# project1.net
KiCad netlist of a schematic drawn in EAGLE
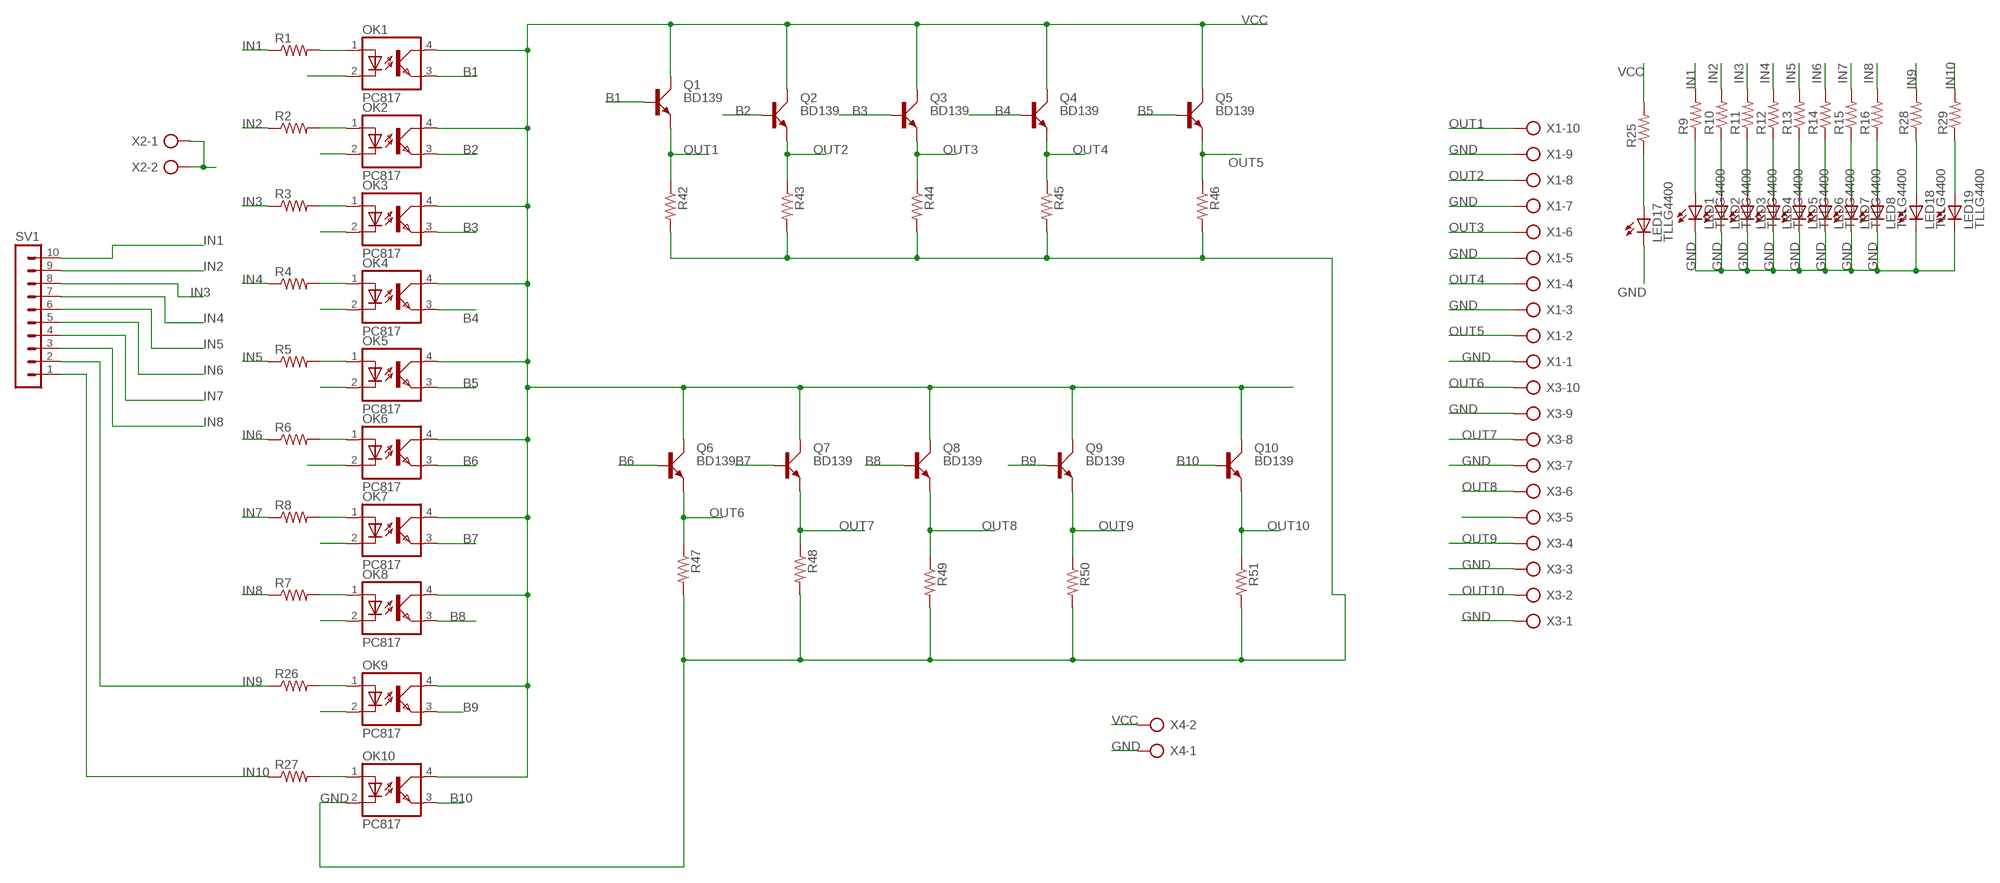
[diagram p0: schematic, sheet 1]

(export (version "E")
  (design (tool "Eeschema 10.0.6"))
  (components
    (comp (ref "LED1")
      (value "TLLG4400")
      (footprint "eagle-import:LED3MM")
      (fields (field (name "MF") "VISHAY SEMICONDUCTOR"))
      (libsource (lib "eagle-import") (part "TLLG4400"))
    )
    (comp (ref "LED2")
      (value "TLLG4400")
      (footprint "eagle-import:LED3MM")
      (fields (field (name "MF") "VISHAY SEMICONDUCTOR"))
      (libsource (lib "eagle-import") (part "TLLG4400"))
    )
    (comp (ref "LED3")
      (value "TLLG4400")
      (footprint "eagle-import:LED3MM")
      (fields (field (name "MF") "VISHAY SEMICONDUCTOR"))
      (libsource (lib "eagle-import") (part "TLLG4400"))
    )
    (comp (ref "LED4")
      (value "TLLG4400")
      (footprint "eagle-import:LED3MM")
      (fields (field (name "MF") "VISHAY SEMICONDUCTOR"))
      (libsource (lib "eagle-import") (part "TLLG4400"))
    )
    (comp (ref "LED5")
      (value "TLLG4400")
      (footprint "eagle-import:LED3MM")
      (fields (field (name "MF") "VISHAY SEMICONDUCTOR"))
      (libsource (lib "eagle-import") (part "TLLG4400"))
    )
    (comp (ref "LED6")
      (value "TLLG4400")
      (footprint "eagle-import:LED3MM")
      (fields (field (name "MF") "VISHAY SEMICONDUCTOR"))
      (libsource (lib "eagle-import") (part "TLLG4400"))
    )
    (comp (ref "LED7")
      (value "TLLG4400")
      (footprint "eagle-import:LED3MM")
      (fields (field (name "MF") "VISHAY SEMICONDUCTOR"))
      (libsource (lib "eagle-import") (part "TLLG4400"))
    )
    (comp (ref "LED8")
      (value "TLLG4400")
      (footprint "eagle-import:LED3MM")
      (fields (field (name "MF") "VISHAY SEMICONDUCTOR"))
      (libsource (lib "eagle-import") (part "TLLG4400"))
    )
    (comp (ref "LED17")
      (value "TLLG4400")
      (footprint "eagle-import:LED3MM")
      (fields (field (name "MF") "VISHAY SEMICONDUCTOR"))
      (libsource (lib "eagle-import") (part "TLLG4400"))
    )
    (comp (ref "LED18")
      (value "TLLG4400")
      (footprint "eagle-import:LED3MM")
      (fields (field (name "MF") "VISHAY SEMICONDUCTOR"))
      (libsource (lib "eagle-import") (part "TLLG4400"))
    )
    (comp (ref "LED19")
      (value "TLLG4400")
      (footprint "eagle-import:LED3MM")
      (fields (field (name "MF") "VISHAY SEMICONDUCTOR"))
      (libsource (lib "eagle-import") (part "TLLG4400"))
    )
    (comp (ref "OK1")
      (value "PC817")
      (footprint "eagle-import:DIL04")
      (fields (field (name "MPN") "PC817X4J000F"))
      (libsource (lib "eagle-import") (part "PC817"))
    )
    (comp (ref "OK2")
      (value "PC817")
      (footprint "eagle-import:DIL04")
      (fields (field (name "MPN") "PC817X4J000F"))
      (libsource (lib "eagle-import") (part "PC817"))
    )
    (comp (ref "OK3")
      (value "PC817")
      (footprint "eagle-import:DIL04")
      (fields (field (name "MPN") "PC817X4J000F"))
      (libsource (lib "eagle-import") (part "PC817"))
    )
    (comp (ref "OK4")
      (value "PC817")
      (footprint "eagle-import:DIL04")
      (fields (field (name "MPN") "PC817X4J000F"))
      (libsource (lib "eagle-import") (part "PC817"))
    )
    (comp (ref "OK5")
      (value "PC817")
      (footprint "eagle-import:DIL04")
      (fields (field (name "MPN") "PC817X4J000F"))
      (libsource (lib "eagle-import") (part "PC817"))
    )
    (comp (ref "OK6")
      (value "PC817")
      (footprint "eagle-import:DIL04")
      (fields (field (name "MPN") "PC817X4J000F"))
      (libsource (lib "eagle-import") (part "PC817"))
    )
    (comp (ref "OK7")
      (value "PC817")
      (footprint "eagle-import:DIL04")
      (fields (field (name "MPN") "PC817X4J000F"))
      (libsource (lib "eagle-import") (part "PC817"))
    )
    (comp (ref "OK8")
      (value "PC817")
      (footprint "eagle-import:DIL04")
      (fields (field (name "MPN") "PC817X4J000F"))
      (libsource (lib "eagle-import") (part "PC817"))
    )
    (comp (ref "OK9")
      (value "PC817")
      (footprint "eagle-import:DIL04")
      (fields (field (name "MPN") "PC817X4J000F"))
      (libsource (lib "eagle-import") (part "PC817"))
    )
    (comp (ref "OK10")
      (value "PC817")
      (footprint "eagle-import:DIL04")
      (fields (field (name "MPN") "PC817X4J000F"))
      (libsource (lib "eagle-import") (part "PC817"))
    )
    (comp (ref "Q1")
      (value "BD139")
      (footprint "eagle-import:TO126AV")
      (libsource (lib "eagle-import") (part "BD139"))
    )
    (comp (ref "Q2")
      (value "BD139")
      (footprint "eagle-import:TO126AV")
      (libsource (lib "eagle-import") (part "BD139"))
    )
    (comp (ref "Q3")
      (value "BD139")
      (footprint "eagle-import:TO126AV")
      (libsource (lib "eagle-import") (part "BD139"))
    )
    (comp (ref "Q4")
      (value "BD139")
      (footprint "eagle-import:TO126AV")
      (libsource (lib "eagle-import") (part "BD139"))
    )
    (comp (ref "Q5")
      (value "BD139")
      (footprint "eagle-import:TO126AV")
      (libsource (lib "eagle-import") (part "BD139"))
    )
    (comp (ref "Q6")
      (value "BD139")
      (footprint "eagle-import:TO126AV")
      (libsource (lib "eagle-import") (part "BD139"))
    )
    (comp (ref "Q7")
      (value "BD139")
      (footprint "eagle-import:TO126AV")
      (libsource (lib "eagle-import") (part "BD139"))
    )
    (comp (ref "Q8")
      (value "BD139")
      (footprint "eagle-import:TO126AV")
      (libsource (lib "eagle-import") (part "BD139"))
    )
    (comp (ref "Q9")
      (value "BD139")
      (footprint "eagle-import:TO126AV")
      (libsource (lib "eagle-import") (part "BD139"))
    )
    (comp (ref "Q10")
      (value "BD139")
      (footprint "eagle-import:TO126AV")
      (libsource (lib "eagle-import") (part "BD139"))
    )
    (comp (ref "R1")
      (value "R-US_0207/10")
      (footprint "eagle-import:0207_10")
      (libsource (lib "eagle-import") (part "resistor_R-US_0207/10"))
    )
    (comp (ref "R2")
      (value "R-US_0207/10")
      (footprint "eagle-import:0207_10")
      (libsource (lib "eagle-import") (part "R-US_0207/10"))
    )
    (comp (ref "R3")
      (value "R-US_0207/10")
      (footprint "eagle-import:0207_10")
      (libsource (lib "eagle-import") (part "R-US_0207/10"))
    )
    (comp (ref "R4")
      (value "R-US_0207/10")
      (footprint "eagle-import:0207_10")
      (libsource (lib "eagle-import") (part "R-US_0207/10"))
    )
    (comp (ref "R5")
      (value "R-US_0207/10")
      (footprint "eagle-import:0207_10")
      (libsource (lib "eagle-import") (part "R-US_0207/10"))
    )
    (comp (ref "R6")
      (value "R-US_0207/10")
      (footprint "eagle-import:0207_10")
      (libsource (lib "eagle-import") (part "R-US_0207/10"))
    )
    (comp (ref "R7")
      (value "R-US_0207/10")
      (footprint "eagle-import:0207_10")
      (libsource (lib "eagle-import") (part "R-US_0207/10"))
    )
    (comp (ref "R8")
      (value "R-US_0207/10")
      (footprint "eagle-import:0207_10")
      (libsource (lib "eagle-import") (part "R-US_0207/10"))
    )
    (comp (ref "R9")
      (value "R-US_0207/10")
      (footprint "eagle-import:0207_10")
      (libsource (lib "eagle-import") (part "R-US_0207/10"))
    )
    (comp (ref "R10")
      (value "R-US_0207/10")
      (footprint "eagle-import:0207_10")
      (libsource (lib "eagle-import") (part "R-US_0207/10"))
    )
    (comp (ref "R11")
      (value "R-US_0207/10")
      (footprint "eagle-import:0207_10")
      (libsource (lib "eagle-import") (part "R-US_0207/10"))
    )
    (comp (ref "R12")
      (value "R-US_0207/10")
      (footprint "eagle-import:0207_10")
      (libsource (lib "eagle-import") (part "R-US_0207/10"))
    )
    (comp (ref "R13")
      (value "R-US_0207/10")
      (footprint "eagle-import:0207_10")
      (libsource (lib "eagle-import") (part "R-US_0207/10"))
    )
    (comp (ref "R14")
      (value "R-US_0207/10")
      (footprint "eagle-import:0207_10")
      (libsource (lib "eagle-import") (part "R-US_0207/10"))
    )
    (comp (ref "R15")
      (value "R-US_0207/10")
      (footprint "eagle-import:0207_10")
      (libsource (lib "eagle-import") (part "R-US_0207/10"))
    )
    (comp (ref "R16")
      (value "R-US_0207/10")
      (footprint "eagle-import:0207_10")
      (libsource (lib "eagle-import") (part "R-US_0207/10"))
    )
    (comp (ref "R25")
      (value "R-US_0207/10")
      (footprint "eagle-import:0207_10")
      (libsource (lib "eagle-import") (part "R-US_0207/10"))
    )
    (comp (ref "R26")
      (value "R-US_0207/10")
      (footprint "eagle-import:0207_10")
      (libsource (lib "eagle-import") (part "R-US_0207/10"))
    )
    (comp (ref "R27")
      (value "R-US_0207/10")
      (footprint "eagle-import:0207_10")
      (libsource (lib "eagle-import") (part "R-US_0207/10"))
    )
    (comp (ref "R28")
      (value "R-US_0207/10")
      (footprint "eagle-import:0207_10")
      (libsource (lib "eagle-import") (part "R-US_0207/10"))
    )
    (comp (ref "R29")
      (value "R-US_0207/10")
      (footprint "eagle-import:0207_10")
      (libsource (lib "eagle-import") (part "R-US_0207/10"))
    )
    (comp (ref "R42")
      (value "R-US_0207/10")
      (footprint "eagle-import:0207_10")
      (libsource (lib "eagle-import") (part "resistor_R-US_0207/10"))
    )
    (comp (ref "R43")
      (value "R-US_0207/10")
      (footprint "eagle-import:0207_10")
      (libsource (lib "eagle-import") (part "resistor_R-US_0207/10"))
    )
    (comp (ref "R44")
      (value "R-US_0207/10")
      (footprint "eagle-import:0207_10")
      (libsource (lib "eagle-import") (part "resistor_R-US_0207/10"))
    )
    (comp (ref "R45")
      (value "R-US_0207/10")
      (footprint "eagle-import:0207_10")
      (libsource (lib "eagle-import") (part "resistor_R-US_0207/10"))
    )
    (comp (ref "R46")
      (value "R-US_0207/10")
      (footprint "eagle-import:0207_10")
      (libsource (lib "eagle-import") (part "resistor_R-US_0207/10"))
    )
    (comp (ref "R47")
      (value "R-US_0207/10")
      (footprint "eagle-import:0207_10")
      (libsource (lib "eagle-import") (part "resistor_R-US_0207/10"))
    )
    (comp (ref "R48")
      (value "R-US_0207/10")
      (footprint "eagle-import:0207_10")
      (libsource (lib "eagle-import") (part "resistor_R-US_0207/10"))
    )
    (comp (ref "R49")
      (value "R-US_0207/10")
      (footprint "eagle-import:0207_10")
      (libsource (lib "eagle-import") (part "resistor_R-US_0207/10"))
    )
    (comp (ref "R50")
      (value "R-US_0207/10")
      (footprint "eagle-import:0207_10")
      (libsource (lib "eagle-import") (part "resistor_R-US_0207/10"))
    )
    (comp (ref "R51")
      (value "R-US_0207/10")
      (footprint "eagle-import:0207_10")
      (libsource (lib "eagle-import") (part "resistor_R-US_0207/10"))
    )
    (comp (ref "SV1")
      (value "MA10-1")
      (footprint "eagle-import:MA10-1")
      (libsource (lib "eagle-import") (part "MA10-1"))
    )
    (comp (ref "X1")
      (value "AK300/10")
      (footprint "eagle-import:AK300_10")
      (libsource (lib "eagle-import") (part "AK300/10"))
    )
    (comp (ref "X2")
      (value "AK300/2")
      (footprint "eagle-import:AK300_2")
      (libsource (lib "eagle-import") (part "AK300/2"))
    )
    (comp (ref "X3")
      (value "AK300/10")
      (footprint "eagle-import:AK300_10")
      (libsource (lib "eagle-import") (part "AK300/10"))
    )
    (comp (ref "X4")
      (value "AK300/2")
      (footprint "eagle-import:AK300_2")
      (libsource (lib "eagle-import") (part "AK300/2"))
    )
  )
  (nets
    (net (code "1") (name "/B1") (class "Default")
      (node (ref "OK1") (pin "3") (pinfunction "EMIT_3") (pintype "passive"))
      (node (ref "Q1") (pin "B") (pinfunction "B_B") (pintype "passive"))
    )
    (net (code "2") (name "/B2") (class "Default")
      (node (ref "OK2") (pin "3") (pinfunction "EMIT_3") (pintype "passive"))
      (node (ref "Q2") (pin "B") (pinfunction "B_B") (pintype "passive"))
    )
    (net (code "3") (name "/B3") (class "Default")
      (node (ref "OK3") (pin "3") (pinfunction "EMIT_3") (pintype "passive"))
      (node (ref "Q3") (pin "B") (pinfunction "B_B") (pintype "passive"))
    )
    (net (code "4") (name "/B4") (class "Default")
      (node (ref "OK4") (pin "3") (pinfunction "EMIT_3") (pintype "passive"))
      (node (ref "Q4") (pin "B") (pinfunction "B_B") (pintype "passive"))
    )
    (net (code "5") (name "/B5") (class "Default")
      (node (ref "OK5") (pin "3") (pinfunction "EMIT_3") (pintype "passive"))
      (node (ref "Q5") (pin "B") (pinfunction "B_B") (pintype "passive"))
    )
    (net (code "6") (name "/B6") (class "Default")
      (node (ref "OK6") (pin "3") (pinfunction "EMIT_3") (pintype "passive"))
      (node (ref "Q6") (pin "B") (pinfunction "B_B") (pintype "passive"))
    )
    (net (code "7") (name "/B7") (class "Default")
      (node (ref "OK7") (pin "3") (pinfunction "EMIT_3") (pintype "passive"))
      (node (ref "Q7") (pin "B") (pinfunction "B_B") (pintype "passive"))
    )
    (net (code "8") (name "/B8") (class "Default")
      (node (ref "OK8") (pin "3") (pinfunction "EMIT_3") (pintype "passive"))
      (node (ref "Q8") (pin "B") (pinfunction "B_B") (pintype "passive"))
    )
    (net (code "9") (name "/B9") (class "Default")
      (node (ref "OK9") (pin "3") (pinfunction "EMIT_3") (pintype "passive"))
      (node (ref "Q9") (pin "B") (pinfunction "B_B") (pintype "passive"))
    )
    (net (code "10") (name "/B10") (class "Default")
      (node (ref "OK10") (pin "3") (pinfunction "EMIT_3") (pintype "passive"))
      (node (ref "Q10") (pin "B") (pinfunction "B_B") (pintype "passive"))
    )
    (net (code "11") (name "/GND") (class "Default")
      (node (ref "LED1") (pin "K") (pinfunction "C_K") (pintype "passive"))
      (node (ref "LED17") (pin "K") (pinfunction "C_K") (pintype "passive"))
      (node (ref "LED18") (pin "K") (pinfunction "C_K") (pintype "passive"))
      (node (ref "LED19") (pin "K") (pinfunction "C_K") (pintype "passive"))
      (node (ref "LED2") (pin "K") (pinfunction "C_K") (pintype "passive"))
      (node (ref "LED3") (pin "K") (pinfunction "C_K") (pintype "passive"))
      (node (ref "LED4") (pin "K") (pinfunction "C_K") (pintype "passive"))
      (node (ref "LED5") (pin "K") (pinfunction "C_K") (pintype "passive"))
      (node (ref "LED6") (pin "K") (pinfunction "C_K") (pintype "passive"))
      (node (ref "LED7") (pin "K") (pinfunction "C_K") (pintype "passive"))
      (node (ref "LED8") (pin "K") (pinfunction "C_K") (pintype "passive"))
      (node (ref "OK1") (pin "2") (pinfunction "C_2") (pintype "passive"))
      (node (ref "OK10") (pin "2") (pinfunction "C_2") (pintype "passive"))
      (node (ref "OK2") (pin "2") (pinfunction "C_2") (pintype "passive"))
      (node (ref "OK3") (pin "2") (pinfunction "C_2") (pintype "passive"))
      (node (ref "OK4") (pin "2") (pinfunction "C_2") (pintype "passive"))
      (node (ref "OK5") (pin "2") (pinfunction "C_2") (pintype "passive"))
      (node (ref "OK6") (pin "2") (pinfunction "C_2") (pintype "passive"))
      (node (ref "OK7") (pin "2") (pinfunction "C_2") (pintype "passive"))
      (node (ref "OK8") (pin "2") (pinfunction "C_2") (pintype "passive"))
      (node (ref "OK9") (pin "2") (pinfunction "C_2") (pintype "passive"))
      (node (ref "R42") (pin "2") (pinfunction "2_2") (pintype "passive"))
      (node (ref "R43") (pin "2") (pinfunction "2_2") (pintype "passive"))
      (node (ref "R44") (pin "2") (pinfunction "2_2") (pintype "passive"))
      (node (ref "R45") (pin "2") (pinfunction "2_2") (pintype "passive"))
      (node (ref "R46") (pin "2") (pinfunction "2_2") (pintype "passive"))
      (node (ref "R47") (pin "2") (pinfunction "2_2") (pintype "passive"))
      (node (ref "R48") (pin "2") (pinfunction "2_2") (pintype "passive"))
      (node (ref "R49") (pin "2") (pinfunction "2_2") (pintype "passive"))
      (node (ref "R50") (pin "2") (pinfunction "2_2") (pintype "passive"))
      (node (ref "R51") (pin "2") (pinfunction "2_2") (pintype "passive"))
      (node (ref "X1") (pin "1") (pinfunction "KL_1") (pintype "passive"))
      (node (ref "X1") (pin "3") (pinfunction "KL_3") (pintype "passive"))
      (node (ref "X1") (pin "5") (pinfunction "KL_5") (pintype "passive"))
      (node (ref "X1") (pin "7") (pinfunction "KL_7") (pintype "passive"))
      (node (ref "X1") (pin "9") (pinfunction "KL_9") (pintype "passive"))
      (node (ref "X2") (pin "1") (pinfunction "KL_1") (pintype "passive"))
      (node (ref "X2") (pin "2") (pinfunction "KL_2") (pintype "passive"))
      (node (ref "X3") (pin "1") (pinfunction "KL_1") (pintype "passive"))
      (node (ref "X3") (pin "3") (pinfunction "KL_3") (pintype "passive"))
      (node (ref "X3") (pin "5") (pinfunction "KL_5") (pintype "passive"))
      (node (ref "X3") (pin "7") (pinfunction "KL_7") (pintype "passive"))
      (node (ref "X3") (pin "9") (pinfunction "KL_9") (pintype "passive"))
      (node (ref "X4") (pin "1") (pinfunction "KL_1") (pintype "passive"))
    )
    (net (code "12") (name "/IN1") (class "Default")
      (node (ref "R1") (pin "1") (pinfunction "1_1") (pintype "passive"))
      (node (ref "R9") (pin "2") (pinfunction "2_2") (pintype "passive"))
      (node (ref "SV1") (pin "10") (pinfunction "10_10") (pintype "passive"))
    )
    (net (code "13") (name "/IN2") (class "Default")
      (node (ref "R10") (pin "2") (pinfunction "2_2") (pintype "passive"))
      (node (ref "R2") (pin "1") (pinfunction "1_1") (pintype "passive"))
      (node (ref "SV1") (pin "9") (pinfunction "9_9") (pintype "passive"))
    )
    (net (code "14") (name "/IN3") (class "Default")
      (node (ref "R11") (pin "2") (pinfunction "2_2") (pintype "passive"))
      (node (ref "R3") (pin "1") (pinfunction "1_1") (pintype "passive"))
      (node (ref "SV1") (pin "8") (pinfunction "8_8") (pintype "passive"))
    )
    (net (code "15") (name "/IN4") (class "Default")
      (node (ref "R12") (pin "2") (pinfunction "2_2") (pintype "passive"))
      (node (ref "R4") (pin "1") (pinfunction "1_1") (pintype "passive"))
      (node (ref "SV1") (pin "7") (pinfunction "7_7") (pintype "passive"))
    )
    (net (code "16") (name "/IN5") (class "Default")
      (node (ref "R13") (pin "2") (pinfunction "2_2") (pintype "passive"))
      (node (ref "R5") (pin "1") (pinfunction "1_1") (pintype "passive"))
      (node (ref "SV1") (pin "6") (pinfunction "6_6") (pintype "passive"))
    )
    (net (code "17") (name "/IN6") (class "Default")
      (node (ref "R14") (pin "2") (pinfunction "2_2") (pintype "passive"))
      (node (ref "R6") (pin "1") (pinfunction "1_1") (pintype "passive"))
      (node (ref "SV1") (pin "5") (pinfunction "5_5") (pintype "passive"))
    )
    (net (code "18") (name "/IN7") (class "Default")
      (node (ref "R15") (pin "2") (pinfunction "2_2") (pintype "passive"))
      (node (ref "R8") (pin "1") (pinfunction "1_1") (pintype "passive"))
      (node (ref "SV1") (pin "4") (pinfunction "4_4") (pintype "passive"))
    )
    (net (code "19") (name "/IN8") (class "Default")
      (node (ref "R16") (pin "2") (pinfunction "2_2") (pintype "passive"))
      (node (ref "R7") (pin "1") (pinfunction "1_1") (pintype "passive"))
      (node (ref "SV1") (pin "3") (pinfunction "3_3") (pintype "passive"))
    )
    (net (code "20") (name "/IN9") (class "Default")
      (node (ref "R26") (pin "1") (pinfunction "1_1") (pintype "passive"))
      (node (ref "R28") (pin "2") (pinfunction "2_2") (pintype "passive"))
      (node (ref "SV1") (pin "2") (pinfunction "2_2") (pintype "passive"))
    )
    (net (code "21") (name "/IN10") (class "Default")
      (node (ref "R27") (pin "1") (pinfunction "1_1") (pintype "passive"))
      (node (ref "R29") (pin "2") (pinfunction "2_2") (pintype "passive"))
      (node (ref "SV1") (pin "1") (pinfunction "1_1") (pintype "passive"))
    )
    (net (code "22") (name "/OUT1") (class "Default")
      (node (ref "Q1") (pin "E") (pinfunction "E_E") (pintype "passive"))
      (node (ref "R42") (pin "1") (pinfunction "1_1") (pintype "passive"))
      (node (ref "X1") (pin "10") (pinfunction "KL_10") (pintype "passive"))
    )
    (net (code "23") (name "/OUT2") (class "Default")
      (node (ref "Q2") (pin "E") (pinfunction "E_E") (pintype "passive"))
      (node (ref "R43") (pin "1") (pinfunction "1_1") (pintype "passive"))
      (node (ref "X1") (pin "8") (pinfunction "KL_8") (pintype "passive"))
    )
    (net (code "24") (name "/OUT3") (class "Default")
      (node (ref "Q3") (pin "E") (pinfunction "E_E") (pintype "passive"))
      (node (ref "R44") (pin "1") (pinfunction "1_1") (pintype "passive"))
      (node (ref "X1") (pin "6") (pinfunction "KL_6") (pintype "passive"))
    )
    (net (code "25") (name "/OUT4") (class "Default")
      (node (ref "Q4") (pin "E") (pinfunction "E_E") (pintype "passive"))
      (node (ref "R45") (pin "1") (pinfunction "1_1") (pintype "passive"))
      (node (ref "X1") (pin "4") (pinfunction "KL_4") (pintype "passive"))
    )
    (net (code "26") (name "/OUT5") (class "Default")
      (node (ref "Q5") (pin "E") (pinfunction "E_E") (pintype "passive"))
      (node (ref "R46") (pin "1") (pinfunction "1_1") (pintype "passive"))
      (node (ref "X1") (pin "2") (pinfunction "KL_2") (pintype "passive"))
    )
    (net (code "27") (name "/OUT6") (class "Default")
      (node (ref "Q6") (pin "E") (pinfunction "E_E") (pintype "passive"))
      (node (ref "R47") (pin "1") (pinfunction "1_1") (pintype "passive"))
      (node (ref "X3") (pin "10") (pinfunction "KL_10") (pintype "passive"))
    )
    (net (code "28") (name "/OUT7") (class "Default")
      (node (ref "Q7") (pin "E") (pinfunction "E_E") (pintype "passive"))
      (node (ref "R48") (pin "1") (pinfunction "1_1") (pintype "passive"))
      (node (ref "X3") (pin "8") (pinfunction "KL_8") (pintype "passive"))
    )
    (net (code "29") (name "/OUT8") (class "Default")
      (node (ref "Q8") (pin "E") (pinfunction "E_E") (pintype "passive"))
      (node (ref "R49") (pin "1") (pinfunction "1_1") (pintype "passive"))
      (node (ref "X3") (pin "6") (pinfunction "KL_6") (pintype "passive"))
    )
    (net (code "30") (name "/OUT9") (class "Default")
      (node (ref "Q9") (pin "E") (pinfunction "E_E") (pintype "passive"))
      (node (ref "R50") (pin "1") (pinfunction "1_1") (pintype "passive"))
      (node (ref "X3") (pin "4") (pinfunction "KL_4") (pintype "passive"))
    )
    (net (code "31") (name "/OUT10") (class "Default")
      (node (ref "Q10") (pin "E") (pinfunction "E_E") (pintype "passive"))
      (node (ref "R51") (pin "1") (pinfunction "1_1") (pintype "passive"))
      (node (ref "X3") (pin "2") (pinfunction "KL_2") (pintype "passive"))
    )
    (net (code "32") (name "/VCC") (class "Default")
      (node (ref "OK1") (pin "4") (pinfunction "COL_4") (pintype "passive"))
      (node (ref "OK10") (pin "4") (pinfunction "COL_4") (pintype "passive"))
      (node (ref "OK2") (pin "4") (pinfunction "COL_4") (pintype "passive"))
      (node (ref "OK3") (pin "4") (pinfunction "COL_4") (pintype "passive"))
      (node (ref "OK4") (pin "4") (pinfunction "COL_4") (pintype "passive"))
      (node (ref "OK5") (pin "4") (pinfunction "COL_4") (pintype "passive"))
      (node (ref "OK6") (pin "4") (pinfunction "COL_4") (pintype "passive"))
      (node (ref "OK7") (pin "4") (pinfunction "COL_4") (pintype "passive"))
      (node (ref "OK8") (pin "4") (pinfunction "COL_4") (pintype "passive"))
      (node (ref "OK9") (pin "4") (pinfunction "COL_4") (pintype "passive"))
      (node (ref "Q1") (pin "C") (pinfunction "C_C") (pintype "passive"))
      (node (ref "Q10") (pin "C") (pinfunction "C_C") (pintype "passive"))
      (node (ref "Q2") (pin "C") (pinfunction "C_C") (pintype "passive"))
      (node (ref "Q3") (pin "C") (pinfunction "C_C") (pintype "passive"))
      (node (ref "Q4") (pin "C") (pinfunction "C_C") (pintype "passive"))
      (node (ref "Q5") (pin "C") (pinfunction "C_C") (pintype "passive"))
      (node (ref "Q6") (pin "C") (pinfunction "C_C") (pintype "passive"))
      (node (ref "Q7") (pin "C") (pinfunction "C_C") (pintype "passive"))
      (node (ref "Q8") (pin "C") (pinfunction "C_C") (pintype "passive"))
      (node (ref "Q9") (pin "C") (pinfunction "C_C") (pintype "passive"))
      (node (ref "R25") (pin "2") (pinfunction "2_2") (pintype "passive"))
      (node (ref "X4") (pin "2") (pinfunction "KL_2") (pintype "passive"))
    )
    (net (code "33") (name "Net-(LED1-PadA)") (class "Default")
      (node (ref "LED1") (pin "A") (pinfunction "A_A") (pintype "passive"))
      (node (ref "R9") (pin "1") (pinfunction "1_1") (pintype "passive"))
    )
    (net (code "34") (name "Net-(LED2-PadA)") (class "Default")
      (node (ref "LED2") (pin "A") (pinfunction "A_A") (pintype "passive"))
      (node (ref "R10") (pin "1") (pinfunction "1_1") (pintype "passive"))
    )
    (net (code "35") (name "Net-(LED3-PadA)") (class "Default")
      (node (ref "LED3") (pin "A") (pinfunction "A_A") (pintype "passive"))
      (node (ref "R11") (pin "1") (pinfunction "1_1") (pintype "passive"))
    )
    (net (code "36") (name "Net-(LED4-PadA)") (class "Default")
      (node (ref "LED4") (pin "A") (pinfunction "A_A") (pintype "passive"))
      (node (ref "R12") (pin "1") (pinfunction "1_1") (pintype "passive"))
    )
    (net (code "37") (name "Net-(LED5-PadA)") (class "Default")
      (node (ref "LED5") (pin "A") (pinfunction "A_A") (pintype "passive"))
      (node (ref "R13") (pin "1") (pinfunction "1_1") (pintype "passive"))
    )
    (net (code "38") (name "Net-(LED6-PadA)") (class "Default")
      (node (ref "LED6") (pin "A") (pinfunction "A_A") (pintype "passive"))
      (node (ref "R14") (pin "1") (pinfunction "1_1") (pintype "passive"))
    )
    (net (code "39") (name "Net-(LED7-PadA)") (class "Default")
      (node (ref "LED7") (pin "A") (pinfunction "A_A") (pintype "passive"))
      (node (ref "R15") (pin "1") (pinfunction "1_1") (pintype "passive"))
    )
    (net (code "40") (name "Net-(LED8-PadA)") (class "Default")
      (node (ref "LED8") (pin "A") (pinfunction "A_A") (pintype "passive"))
      (node (ref "R16") (pin "1") (pinfunction "1_1") (pintype "passive"))
    )
    (net (code "41") (name "Net-(LED17-PadA)") (class "Default")
      (node (ref "LED17") (pin "A") (pinfunction "A_A") (pintype "passive"))
      (node (ref "R25") (pin "1") (pinfunction "1_1") (pintype "passive"))
    )
    (net (code "42") (name "Net-(LED18-PadA)") (class "Default")
      (node (ref "LED18") (pin "A") (pinfunction "A_A") (pintype "passive"))
      (node (ref "R28") (pin "1") (pinfunction "1_1") (pintype "passive"))
    )
    (net (code "43") (name "Net-(LED19-PadA)") (class "Default")
      (node (ref "LED19") (pin "A") (pinfunction "A_A") (pintype "passive"))
      (node (ref "R29") (pin "1") (pinfunction "1_1") (pintype "passive"))
    )
    (net (code "44") (name "Net-(OK1-A)") (class "Default")
      (node (ref "OK1") (pin "1") (pinfunction "A_1") (pintype "passive"))
      (node (ref "R1") (pin "2") (pinfunction "2_2") (pintype "passive"))
    )
    (net (code "45") (name "Net-(OK2-A)") (class "Default")
      (node (ref "OK2") (pin "1") (pinfunction "A_1") (pintype "passive"))
      (node (ref "R2") (pin "2") (pinfunction "2_2") (pintype "passive"))
    )
    (net (code "46") (name "Net-(OK3-A)") (class "Default")
      (node (ref "OK3") (pin "1") (pinfunction "A_1") (pintype "passive"))
      (node (ref "R3") (pin "2") (pinfunction "2_2") (pintype "passive"))
    )
    (net (code "47") (name "Net-(OK4-A)") (class "Default")
      (node (ref "OK4") (pin "1") (pinfunction "A_1") (pintype "passive"))
      (node (ref "R4") (pin "2") (pinfunction "2_2") (pintype "passive"))
    )
    (net (code "48") (name "Net-(OK5-A)") (class "Default")
      (node (ref "OK5") (pin "1") (pinfunction "A_1") (pintype "passive"))
      (node (ref "R5") (pin "2") (pinfunction "2_2") (pintype "passive"))
    )
    (net (code "49") (name "Net-(OK6-A)") (class "Default")
      (node (ref "OK6") (pin "1") (pinfunction "A_1") (pintype "passive"))
      (node (ref "R6") (pin "2") (pinfunction "2_2") (pintype "passive"))
    )
    (net (code "50") (name "Net-(OK7-A)") (class "Default")
      (node (ref "OK7") (pin "1") (pinfunction "A_1") (pintype "passive"))
      (node (ref "R8") (pin "2") (pinfunction "2_2") (pintype "passive"))
    )
    (net (code "51") (name "Net-(OK8-A)") (class "Default")
      (node (ref "OK8") (pin "1") (pinfunction "A_1") (pintype "passive"))
      (node (ref "R7") (pin "2") (pinfunction "2_2") (pintype "passive"))
    )
    (net (code "52") (name "Net-(OK9-A)") (class "Default")
      (node (ref "OK9") (pin "1") (pinfunction "A_1") (pintype "passive"))
      (node (ref "R26") (pin "2") (pinfunction "2_2") (pintype "passive"))
    )
    (net (code "53") (name "Net-(OK10-A)") (class "Default")
      (node (ref "OK10") (pin "1") (pinfunction "A_1") (pintype "passive"))
      (node (ref "R27") (pin "2") (pinfunction "2_2") (pintype "passive"))
    )
  )
)
